# RS485_Interface.net
KiCad netlist of a schematic drawn in Altium Designer
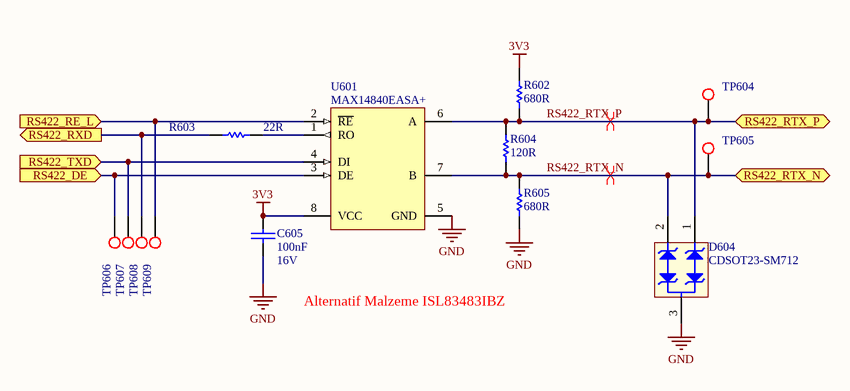
[diagram p0: RS485_Interface.SchDoc]

(export (version "E")
  (design (tool "Eeschema 10.0.6"))
  (components
    (comp (ref "C605")
      (value "100nF")
      (footprint "CAPC1005X06N")
      (description "CAP, CER, X7R, 100nF, %10, 16V, 0402")
      (fields
        (field (name "MANUFACTURER") "Murata")
        (field (name "MANUFACTURER PART NUMBER") "GRM155R71C104KA88D")
        (field (name "OPERATING VOLTAGE") "16V")
      )
      (libsource (lib "Anime_Capacitor") (part "ACC7-2100-S241-0000"))
    )
    (comp (ref "D604")
      (value "CDSOT23-SM712")
      (footprint "SOT95P230X117-3N")
      (description "Diode, TVS, 7V-12V, 400W, CDSOT23-SM712, SOT23")
      (fields (field (name "MANUFACTURER") "Bourns"))
      (libsource (lib "Anime_Semiconductor") (part "AS1H-A17M-SI20-0000"))
    )
    (comp (ref "R602")
      (value "680R")
      (footprint "RESC1005X04N")
      (description "RES, E24, Thick Film, SMD, 680R, 1%, 0.1W, 0402")
      (fields
        (field (name "MANUFACTURER") "Panasonic")
        (field (name "MANUFACTURER PART NUMBER") "ERJ-2RKF6800X")
      )
      (libsource (lib "Anime_Resistor") (part "AR19-2680-S2B2-0000"))
    )
    (comp (ref "R603")
      (value "22R")
      (footprint "RESC1005X04N")
      (description "RES, E24, Thick Film, SMD, 22R, 1%, 0.1W, 0402")
      (fields
        (field (name "MANUFACTURER") "Panasonic")
        (field (name "MANUFACTURER PART NUMBER") "ERJ-2RKF22R0X")
      )
      (libsource (lib "Anime_Resistor") (part "AR19-1220-S2B2-0000"))
    )
    (comp (ref "R604")
      (value "120R")
      (footprint "RESC1005X04N")
      (description "RES, E24, Thick Film, SMD, 120R, 1%, 0.1W, 0402")
      (fields
        (field (name "MANUFACTURER") "Panasonic")
        (field (name "MANUFACTURER PART NUMBER") "ERJ-2RKF1200X")
      )
      (libsource (lib "Anime_Resistor") (part "AR19-2120-S2B2-0000"))
    )
    (comp (ref "R605")
      (value "680R")
      (footprint "RESC1005X04N")
      (description "RES, E24, Thick Film, SMD, 680R, 1%, 0.1W, 0402")
      (fields
        (field (name "MANUFACTURER") "Panasonic")
        (field (name "MANUFACTURER PART NUMBER") "ERJ-2RKF6800X")
      )
      (libsource (lib "Anime_Resistor") (part "AR19-2680-S2B2-0000"))
    )
    (comp (ref "TP604")
      (value "AEMT-C00S-1000-0000")
      (footprint "TP100")
      (description "Test Point, Circular, 1mm")
      (libsource (lib "Anime_Electromechanical") (part "AEMT-C00S-1000-0000"))
    )
    (comp (ref "TP605")
      (value "AEMT-C00S-1000-0000")
      (footprint "TP100")
      (description "Test Point, Circular, 1mm")
      (libsource (lib "Anime_Electromechanical") (part "AEMT-C00S-1000-0000"))
    )
    (comp (ref "TP606")
      (value "AEMT-C00S-1000-0000")
      (footprint "TP100")
      (description "Test Point, Circular, 1mm")
      (libsource (lib "Anime_Electromechanical") (part "AEMT-C00S-1000-0000"))
    )
    (comp (ref "TP607")
      (value "AEMT-C00S-1000-0000")
      (footprint "TP100")
      (description "Test Point, Circular, 1mm")
      (libsource (lib "Anime_Electromechanical") (part "AEMT-C00S-1000-0000"))
    )
    (comp (ref "TP608")
      (value "AEMT-C00S-1000-0000")
      (footprint "TP100")
      (description "Test Point, Circular, 1mm")
      (libsource (lib "Anime_Electromechanical") (part "AEMT-C00S-1000-0000"))
    )
    (comp (ref "TP609")
      (value "AEMT-C00S-1000-0000")
      (footprint "TP100")
      (description "Test Point, Circular, 1mm")
      (libsource (lib "Anime_Electromechanical") (part "AEMT-C00S-1000-0000"))
    )
    (comp (ref "U601")
      (value "MAX14840EASA+")
      (footprint "SOIC127P600X175-8N")
      (description "IC, Interface, Transceiver, RS-485 Half-Dublex, 3.3V, 40Mbps, MAX14840EASA+, SOIC-8")
      (fields (field (name "MANUFACTURER") "MAXIM"))
      (libsource (lib "Anime_IC") (part "AT45-0000-SM50-1120"))
    )
  )
  (nets
    (net (code "1") (name "/RS422_DE") (class "Default")
      (node (ref "TP606") (pin "1") (pintype "passive"))
      (node (ref "U601") (pin "3") (pinfunction "DE_3") (pintype "input"))
    )
    (net (code "2") (name "/RS422_RE_L") (class "Default")
      (node (ref "TP609") (pin "1") (pintype "passive"))
      (node (ref "U601") (pin "2") (pinfunction "~{RE}_2") (pintype "input"))
    )
    (net (code "3") (name "/RS422_RTX_N") (class "Default")
      (node (ref "D604") (pin "2") (pinfunction "2_2") (pintype "passive"))
      (node (ref "R604") (pin "1") (pinfunction "1_1") (pintype "passive"))
      (node (ref "R605") (pin "2") (pinfunction "2_2") (pintype "passive"))
      (node (ref "TP605") (pin "1") (pintype "passive"))
      (node (ref "U601") (pin "7") (pinfunction "B_7") (pintype "passive"))
    )
    (net (code "4") (name "/RS422_RTX_P") (class "Default")
      (node (ref "D604") (pin "1") (pinfunction "1_1") (pintype "passive"))
      (node (ref "R602") (pin "1") (pinfunction "1_1") (pintype "passive"))
      (node (ref "R604") (pin "2") (pinfunction "2_2") (pintype "passive"))
      (node (ref "TP604") (pin "1") (pintype "passive"))
      (node (ref "U601") (pin "6") (pinfunction "A_6") (pintype "passive"))
    )
    (net (code "5") (name "/RS422_RXD") (class "Default")
      (node (ref "R603") (pin "1") (pinfunction "1_1") (pintype "passive"))
      (node (ref "TP608") (pin "1") (pintype "passive"))
    )
    (net (code "6") (name "/RS422_TXD") (class "Default")
      (node (ref "TP607") (pin "1") (pintype "passive"))
      (node (ref "U601") (pin "4") (pinfunction "DI_4") (pintype "input"))
    )
    (net (code "7") (name "3V3") (class "Default")
      (node (ref "C605") (pin "1") (pintype "passive"))
      (node (ref "R602") (pin "2") (pinfunction "2_2") (pintype "passive"))
      (node (ref "U601") (pin "8") (pinfunction "VCC_8") (pintype "power_in"))
    )
    (net (code "8") (name "GND") (class "Default")
      (node (ref "C605") (pin "2") (pintype "passive"))
      (node (ref "D604") (pin "3") (pinfunction "3_3") (pintype "passive"))
      (node (ref "R605") (pin "1") (pinfunction "1_1") (pintype "passive"))
      (node (ref "U601") (pin "5") (pinfunction "GND_5") (pintype "power_in"))
    )
    (net (code "9") (name "Net-(U601-RO)") (class "Default")
      (node (ref "R603") (pin "2") (pinfunction "2_2") (pintype "passive"))
      (node (ref "U601") (pin "1") (pinfunction "RO_1") (pintype "output"))
    )
  )
)
